# 02_Connectors.net
KiCad netlist of a schematic drawn in Altium Designer
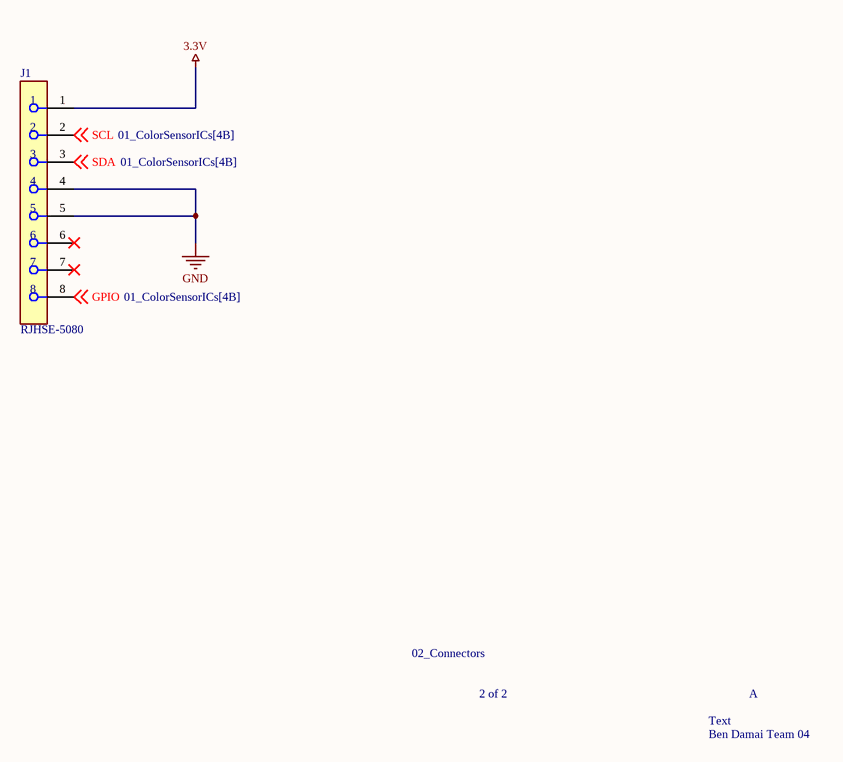
[diagram p0: 02_Connectors.SchDoc]

(export (version "E")
  (design (tool "Eeschema 10.0.6"))
  (components
    (comp (ref "J1")
      (value "RJHSE-5080")
      (footprint "FP-RJHSE-5080-MFG")
      (description "CONN MOD JACK 8P8C R/A UNSHLD")
      (fields
        (field (name "OCTOPART") "https://octopart.com/rjhse-5080-amphenol-45060")
        (field (name "MANUFACTURER") "Amphenol")
      )
      (libsource (lib "Altium Content Vault") (part "b0a0b555dd3abf3683e7c330df25cc4"))
    )
  )
  (nets
    (net (code "1") (name "3.3V") (class "Default")
      (node (ref "J1") (pin "1") (pinfunction "1_1") (pintype "passive"))
    )
    (net (code "2") (name "GND") (class "Default")
      (node (ref "J1") (pin "4") (pinfunction "4_4") (pintype "passive"))
      (node (ref "J1") (pin "5") (pinfunction "5_5") (pintype "passive"))
    )
    (net (code "3") (name "GPIO") (class "Default")
      (node (ref "J1") (pin "8") (pinfunction "8_8") (pintype "passive"))
    )
    (net (code "4") (name "SCL") (class "Default")
      (node (ref "J1") (pin "2") (pinfunction "2_2") (pintype "passive"))
    )
    (net (code "5") (name "SDA") (class "Default")
      (node (ref "J1") (pin "3") (pinfunction "3_3") (pintype "passive"))
    )
    (net (code "6") (name "unconnected-(J1-Pad6)") (class "Default")
      (node (ref "J1") (pin "6") (pinfunction "6_6") (pintype "passive+no_connect"))
    )
    (net (code "7") (name "unconnected-(J1-Pad7)") (class "Default")
      (node (ref "J1") (pin "7") (pinfunction "7_7") (pintype "passive+no_connect"))
    )
  )
)
